# CIC_Arduino_Adapter.net
KiCad netlist of a schematic drawn in EAGLE
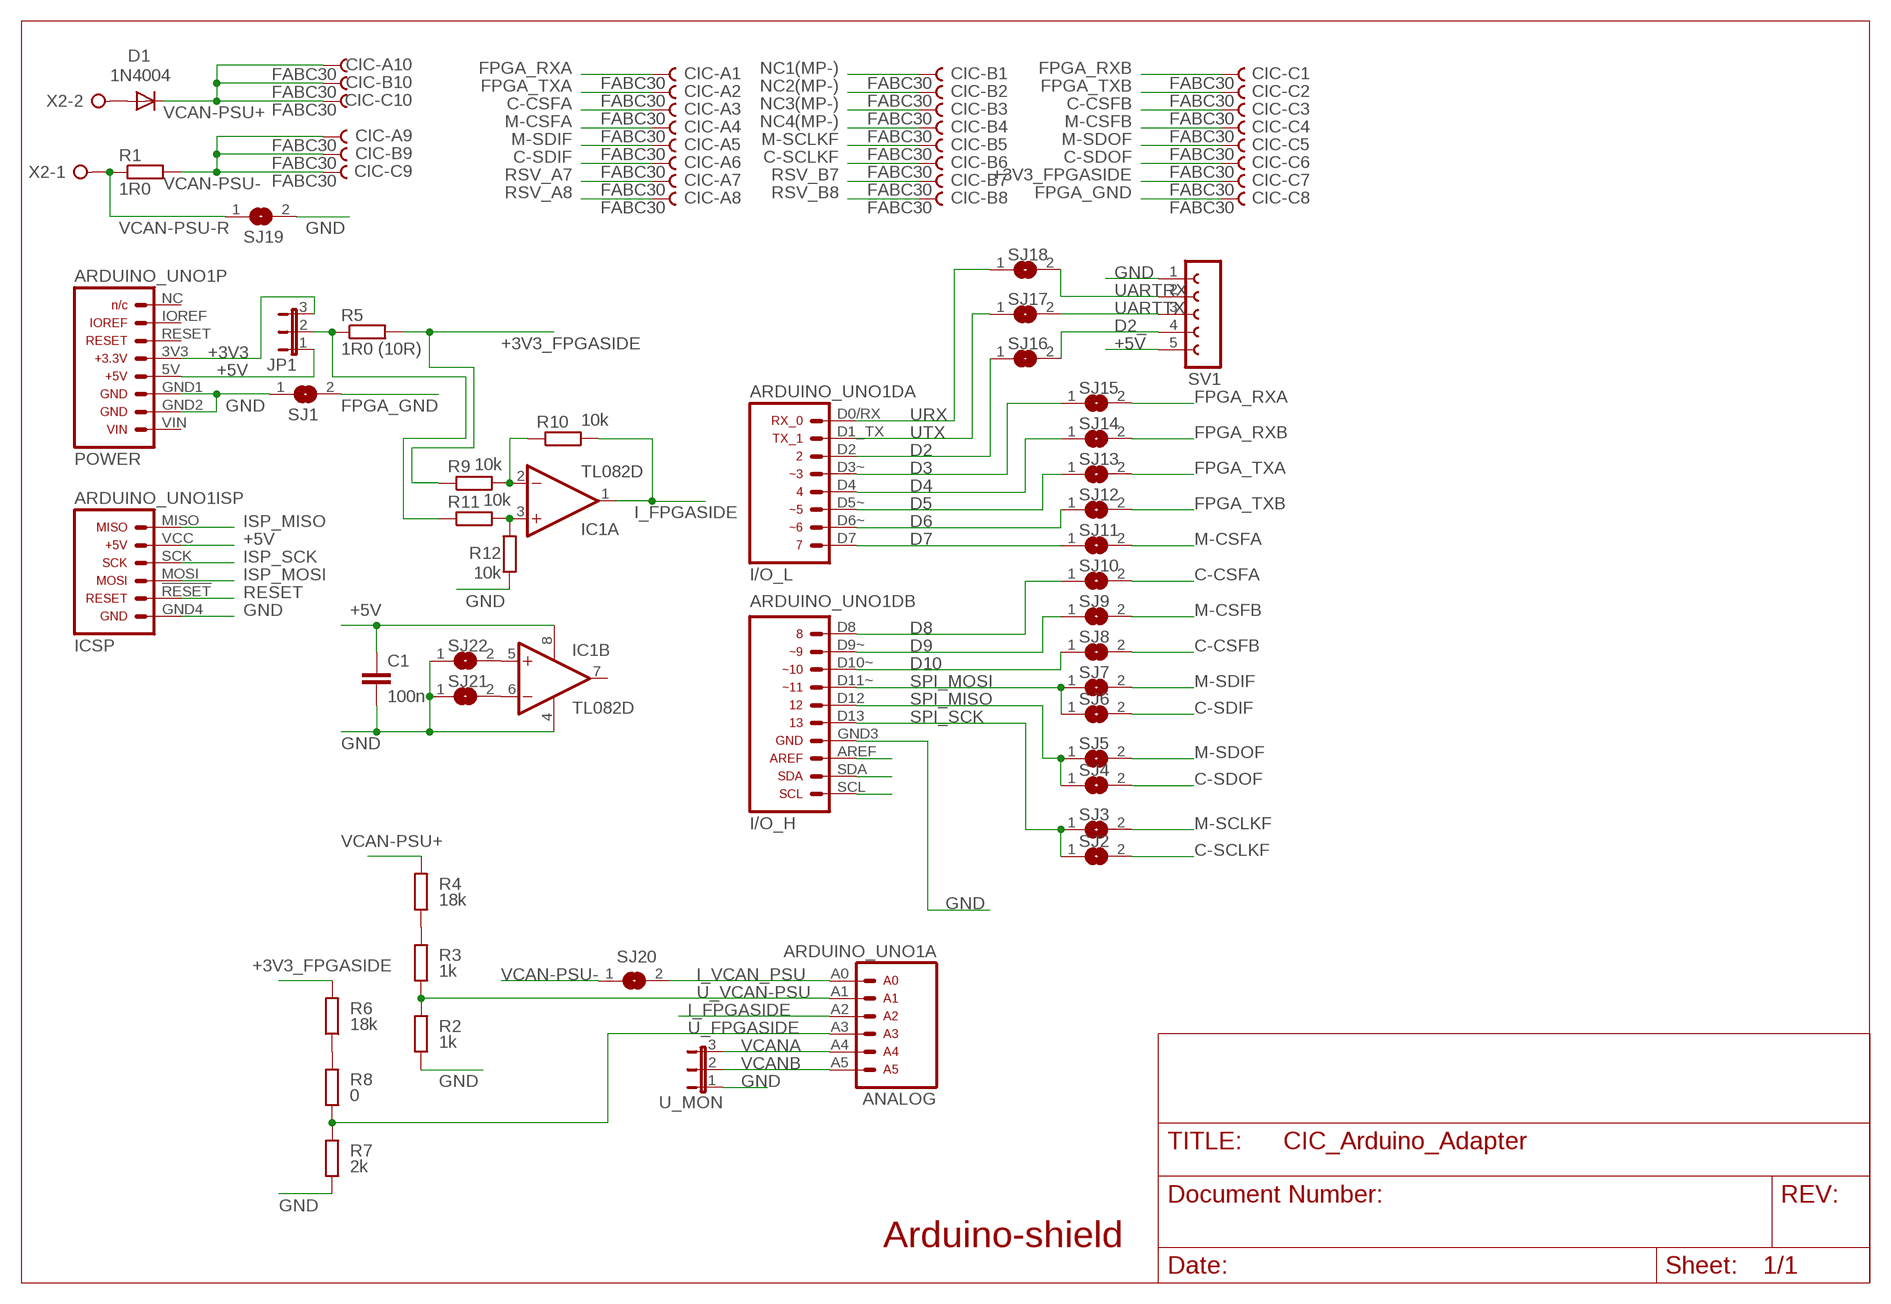
[diagram p0: schematic, sheet 1]

(export (version "E")
  (design (tool "Eeschema 10.0.6"))
  (components
    (comp (ref "ARDUINO_UNO1")
      (value "SHELL_UNO1")
      (footprint "eagle-import:SHELL_UNO_1")
      (libsource (lib "eagle-import") (part "SHELL_UNO1"))
    )
    (comp (ref "C1")
      (value "100n")
      (footprint "eagle-import:C0805")
      (libsource (lib "eagle-import") (part "C-EUC0805"))
    )
    (comp (ref "CIC")
      (value "FABC30")
      (footprint "eagle-import:FABC30")
      (libsource (lib "eagle-import") (part "FABC30"))
    )
    (comp (ref "D1")
      (value "1N4004")
      (footprint "eagle-import:DO41-10")
      (libsource (lib "eagle-import") (part "1N4004"))
    )
    (comp (ref "IC1")
      (value "TL082D")
      (footprint "eagle-import:SO08")
      (libsource (lib "eagle-import") (part "TL082D"))
    )
    (comp (ref "JP1")
      (value "JP2E")
      (footprint "eagle-import:JP2")
      (libsource (lib "eagle-import") (part "JP2E"))
    )
    (comp (ref "R1")
      (value "1R0")
      (footprint "eagle-import:0207_2V")
      (libsource (lib "eagle-import") (part "R-EU_0207/2V"))
    )
    (comp (ref "R2")
      (value "1k")
      (footprint "eagle-import:0207_2V")
      (libsource (lib "eagle-import") (part "R-EU_0207/2V"))
    )
    (comp (ref "R3")
      (value "1k")
      (footprint "eagle-import:0207_2V")
      (libsource (lib "eagle-import") (part "R-EU_0207/2V"))
    )
    (comp (ref "R4")
      (value "18k")
      (footprint "eagle-import:0207_2V")
      (libsource (lib "eagle-import") (part "R-EU_0207/2V"))
    )
    (comp (ref "R5")
      (value "1R0 (10R)")
      (footprint "eagle-import:0207_2V")
      (libsource (lib "eagle-import") (part "R-EU_0207/2V"))
    )
    (comp (ref "R6")
      (value "18k")
      (footprint "eagle-import:0207_2V")
      (libsource (lib "eagle-import") (part "R-EU_0207/2V"))
    )
    (comp (ref "R7")
      (value "2k")
      (footprint "eagle-import:0207_2V")
      (libsource (lib "eagle-import") (part "R-EU_0207/2V"))
    )
    (comp (ref "R8")
      (value "0")
      (footprint "eagle-import:0207_2V")
      (libsource (lib "eagle-import") (part "R-EU_0207/2V"))
    )
    (comp (ref "R9")
      (value "10k")
      (footprint "eagle-import:R0805")
      (libsource (lib "eagle-import") (part "R-EU_R0805"))
    )
    (comp (ref "R10")
      (value "10k")
      (footprint "eagle-import:R0805")
      (libsource (lib "eagle-import") (part "R-EU_R0805"))
    )
    (comp (ref "R11")
      (value "10k")
      (footprint "eagle-import:R0805")
      (libsource (lib "eagle-import") (part "R-EU_R0805"))
    )
    (comp (ref "R12")
      (value "10k")
      (footprint "eagle-import:R0805")
      (libsource (lib "eagle-import") (part "R-EU_R0805"))
    )
    (comp (ref "SJ1") (value "SJ") (footprint "eagle-import:SJ") (libsource (lib "eagle-import") (part "SJ")))
    (comp (ref "SJ2") (value "SJ") (footprint "eagle-import:SJ") (libsource (lib "eagle-import") (part "SJ")))
    (comp (ref "SJ3") (value "SJ") (footprint "eagle-import:SJ") (libsource (lib "eagle-import") (part "SJ")))
    (comp (ref "SJ4") (value "SJ") (footprint "eagle-import:SJ") (libsource (lib "eagle-import") (part "SJ")))
    (comp (ref "SJ5") (value "SJ") (footprint "eagle-import:SJ") (libsource (lib "eagle-import") (part "SJ")))
    (comp (ref "SJ6") (value "SJ") (footprint "eagle-import:SJ") (libsource (lib "eagle-import") (part "SJ")))
    (comp (ref "SJ7") (value "SJ") (footprint "eagle-import:SJ") (libsource (lib "eagle-import") (part "SJ")))
    (comp (ref "SJ8") (value "SJ") (footprint "eagle-import:SJ") (libsource (lib "eagle-import") (part "SJ")))
    (comp (ref "SJ9") (value "SJ") (footprint "eagle-import:SJ") (libsource (lib "eagle-import") (part "SJ")))
    (comp (ref "SJ10")
      (value "SJ")
      (footprint "eagle-import:SJ")
      (libsource (lib "eagle-import") (part "SJ"))
    )
    (comp (ref "SJ11")
      (value "SJ")
      (footprint "eagle-import:SJ")
      (libsource (lib "eagle-import") (part "SJ"))
    )
    (comp (ref "SJ12")
      (value "SJ")
      (footprint "eagle-import:SJ")
      (libsource (lib "eagle-import") (part "SJ"))
    )
    (comp (ref "SJ13")
      (value "SJ")
      (footprint "eagle-import:SJ")
      (libsource (lib "eagle-import") (part "SJ"))
    )
    (comp (ref "SJ14")
      (value "SJ")
      (footprint "eagle-import:SJ")
      (libsource (lib "eagle-import") (part "SJ"))
    )
    (comp (ref "SJ15")
      (value "SJ")
      (footprint "eagle-import:SJ")
      (libsource (lib "eagle-import") (part "SJ"))
    )
    (comp (ref "SJ16")
      (value "SJ")
      (footprint "eagle-import:SJ")
      (libsource (lib "eagle-import") (part "SJ"))
    )
    (comp (ref "SJ17")
      (value "SJ")
      (footprint "eagle-import:SJ")
      (libsource (lib "eagle-import") (part "SJ"))
    )
    (comp (ref "SJ18")
      (value "SJ")
      (footprint "eagle-import:SJ")
      (libsource (lib "eagle-import") (part "SJ"))
    )
    (comp (ref "SJ19")
      (value "SJ")
      (footprint "eagle-import:SJ")
      (libsource (lib "eagle-import") (part "SJ"))
    )
    (comp (ref "SJ20")
      (value "SJ")
      (footprint "eagle-import:SJ")
      (libsource (lib "eagle-import") (part "SJ"))
    )
    (comp (ref "SJ21")
      (value "SJ")
      (footprint "eagle-import:SJ")
      (libsource (lib "eagle-import") (part "SJ"))
    )
    (comp (ref "SJ22")
      (value "SJ")
      (footprint "eagle-import:SJ")
      (libsource (lib "eagle-import") (part "SJ"))
    )
    (comp (ref "SV1")
      (value "FE05-1")
      (footprint "eagle-import:FE05-1")
      (libsource (lib "eagle-import") (part "FE05-1"))
    )
    (comp (ref "U_MON")
      (value "JP2E")
      (footprint "eagle-import:JP2")
      (libsource (lib "eagle-import") (part "JP2E"))
    )
    (comp (ref "X2")
      (value "W237-2N")
      (footprint "eagle-import:W237-2N")
      (libsource (lib "eagle-import") (part "W237-2N"))
    )
  )
  (nets
    (net (code "1") (name "/+3V3") (class "Default")
      (node (ref "ARDUINO_UNO1") (pin "3V3") (pinfunction "4_3V3") (pintype "passive"))
      (node (ref "JP1") (pin "3") (pinfunction "3_3") (pintype "passive"))
    )
    (net (code "2") (name "/+3V3_FPGASIDE") (class "Default")
      (node (ref "CIC") (pin "C7") (pinfunction "B_C7") (pintype "passive"))
      (node (ref "R5") (pin "2") (pinfunction "2_2") (pintype "passive"))
      (node (ref "R6") (pin "2") (pinfunction "2_2") (pintype "passive"))
      (node (ref "R9") (pin "1") (pinfunction "1_1") (pintype "passive"))
    )
    (net (code "3") (name "/+5V") (class "Default")
      (node (ref "ARDUINO_UNO1") (pin "5V") (pinfunction "5_5V") (pintype "passive"))
      (node (ref "ARDUINO_UNO1") (pin "VCC") (pinfunction "2_VCC") (pintype "passive"))
      (node (ref "C1") (pin "1") (pinfunction "1_1") (pintype "passive"))
      (node (ref "IC1") (pin "8") (pinfunction "V+_8") (pintype "power_in"))
      (node (ref "JP1") (pin "1") (pinfunction "1_1") (pintype "passive"))
      (node (ref "SV1") (pin "5") (pinfunction "5_5") (pintype "passive"))
    )
    (net (code "4") (name "/C-CSFA") (class "Default")
      (node (ref "CIC") (pin "A3") (pinfunction "B_A3") (pintype "passive"))
      (node (ref "SJ10") (pin "2") (pinfunction "2_2") (pintype "passive"))
    )
    (net (code "5") (name "/C-CSFB") (class "Default")
      (node (ref "CIC") (pin "C3") (pinfunction "B_C3") (pintype "passive"))
      (node (ref "SJ8") (pin "2") (pinfunction "2_2") (pintype "passive"))
    )
    (net (code "6") (name "/C-SCLKF") (class "Default")
      (node (ref "CIC") (pin "B6") (pinfunction "B_B6") (pintype "passive"))
      (node (ref "SJ2") (pin "2") (pinfunction "2_2") (pintype "passive"))
    )
    (net (code "7") (name "/C-SDIF") (class "Default")
      (node (ref "CIC") (pin "A6") (pinfunction "B_A6") (pintype "passive"))
      (node (ref "SJ6") (pin "2") (pinfunction "2_2") (pintype "passive"))
    )
    (net (code "8") (name "/C-SDOF") (class "Default")
      (node (ref "CIC") (pin "C6") (pinfunction "B_C6") (pintype "passive"))
      (node (ref "SJ4") (pin "2") (pinfunction "2_2") (pintype "passive"))
    )
    (net (code "9") (name "/D2") (class "Default")
      (node (ref "ARDUINO_UNO1") (pin "D2") (pinfunction "3_D2") (pintype "passive"))
      (node (ref "SJ16") (pin "1") (pinfunction "1_1") (pintype "passive"))
    )
    (net (code "10") (name "/D2_") (class "Default")
      (node (ref "SJ16") (pin "2") (pinfunction "2_2") (pintype "passive"))
      (node (ref "SV1") (pin "4") (pinfunction "4_4") (pintype "passive"))
    )
    (net (code "11") (name "/D3") (class "Default")
      (node (ref "ARDUINO_UNO1") (pin "D3~") (pinfunction "4_D3~") (pintype "passive"))
      (node (ref "SJ15") (pin "1") (pinfunction "1_1") (pintype "passive"))
    )
    (net (code "12") (name "/D4") (class "Default")
      (node (ref "ARDUINO_UNO1") (pin "D4") (pinfunction "5_D4") (pintype "passive"))
      (node (ref "SJ14") (pin "1") (pinfunction "1_1") (pintype "passive"))
    )
    (net (code "13") (name "/D5") (class "Default")
      (node (ref "ARDUINO_UNO1") (pin "D5~") (pinfunction "6_D5~") (pintype "passive"))
      (node (ref "SJ13") (pin "1") (pinfunction "1_1") (pintype "passive"))
    )
    (net (code "14") (name "/D6") (class "Default")
      (node (ref "ARDUINO_UNO1") (pin "D6~") (pinfunction "7_D6~") (pintype "passive"))
      (node (ref "SJ12") (pin "1") (pinfunction "1_1") (pintype "passive"))
    )
    (net (code "15") (name "/D7") (class "Default")
      (node (ref "ARDUINO_UNO1") (pin "D7") (pinfunction "8_D7") (pintype "passive"))
      (node (ref "SJ11") (pin "1") (pinfunction "1_1") (pintype "passive"))
    )
    (net (code "16") (name "/D8") (class "Default")
      (node (ref "ARDUINO_UNO1") (pin "D8") (pinfunction "1_D8") (pintype "passive"))
      (node (ref "SJ10") (pin "1") (pinfunction "1_1") (pintype "passive"))
    )
    (net (code "17") (name "/D9") (class "Default")
      (node (ref "ARDUINO_UNO1") (pin "D9~") (pinfunction "2_D9~") (pintype "passive"))
      (node (ref "SJ9") (pin "1") (pinfunction "1_1") (pintype "passive"))
    )
    (net (code "18") (name "/D10") (class "Default")
      (node (ref "ARDUINO_UNO1") (pin "D10~") (pinfunction "3_D10~") (pintype "passive"))
      (node (ref "SJ8") (pin "1") (pinfunction "1_1") (pintype "passive"))
    )
    (net (code "19") (name "/FPGA_GND") (class "Default")
      (node (ref "CIC") (pin "C8") (pinfunction "B_C8") (pintype "passive"))
      (node (ref "SJ1") (pin "2") (pinfunction "2_2") (pintype "passive"))
    )
    (net (code "20") (name "/FPGA_RXA") (class "Default")
      (node (ref "CIC") (pin "A1") (pinfunction "B_A1") (pintype "passive"))
      (node (ref "SJ15") (pin "2") (pinfunction "2_2") (pintype "passive"))
    )
    (net (code "21") (name "/FPGA_RXB") (class "Default")
      (node (ref "CIC") (pin "C1") (pinfunction "B_C1") (pintype "passive"))
      (node (ref "SJ14") (pin "2") (pinfunction "2_2") (pintype "passive"))
    )
    (net (code "22") (name "/FPGA_TXA") (class "Default")
      (node (ref "CIC") (pin "A2") (pinfunction "B_A2") (pintype "passive"))
      (node (ref "SJ13") (pin "2") (pinfunction "2_2") (pintype "passive"))
    )
    (net (code "23") (name "/FPGA_TXB") (class "Default")
      (node (ref "CIC") (pin "C2") (pinfunction "B_C2") (pintype "passive"))
      (node (ref "SJ12") (pin "2") (pinfunction "2_2") (pintype "passive"))
    )
    (net (code "24") (name "/GND") (class "Default")
      (node (ref "ARDUINO_UNO1") (pin "GND1") (pinfunction "6_GND1") (pintype "passive"))
      (node (ref "ARDUINO_UNO1") (pin "GND2") (pinfunction "7_GND2") (pintype "passive"))
      (node (ref "ARDUINO_UNO1") (pin "GND3") (pinfunction "7_GND3") (pintype "passive"))
      (node (ref "ARDUINO_UNO1") (pin "GND4") (pinfunction "6_GND4") (pintype "passive"))
      (node (ref "C1") (pin "2") (pinfunction "2_2") (pintype "passive"))
      (node (ref "IC1") (pin "4") (pinfunction "V-_4") (pintype "power_in"))
      (node (ref "R12") (pin "1") (pinfunction "1_1") (pintype "passive"))
      (node (ref "R2") (pin "1") (pinfunction "1_1") (pintype "passive"))
      (node (ref "R7") (pin "1") (pinfunction "1_1") (pintype "passive"))
      (node (ref "SJ1") (pin "1") (pinfunction "1_1") (pintype "passive"))
      (node (ref "SJ19") (pin "2") (pinfunction "2_2") (pintype "passive"))
      (node (ref "SJ21") (pin "1") (pinfunction "1_1") (pintype "passive"))
      (node (ref "SJ22") (pin "1") (pinfunction "1_1") (pintype "passive"))
      (node (ref "SV1") (pin "1") (pinfunction "1_1") (pintype "passive"))
      (node (ref "U_MON") (pin "1") (pinfunction "1_1") (pintype "passive"))
    )
    (net (code "25") (name "/ISP_MISO") (class "Default")
      (node (ref "ARDUINO_UNO1") (pin "MISO") (pinfunction "1_MISO") (pintype "passive"))
    )
    (net (code "26") (name "/ISP_MOSI") (class "Default")
      (node (ref "ARDUINO_UNO1") (pin "MOSI") (pinfunction "4_MOSI") (pintype "passive"))
    )
    (net (code "27") (name "/ISP_SCK") (class "Default")
      (node (ref "ARDUINO_UNO1") (pin "SCK") (pinfunction "3_SCK") (pintype "passive"))
    )
    (net (code "28") (name "/I_FPGASIDE") (class "Default")
      (node (ref "ARDUINO_UNO1") (pin "A2") (pinfunction "3_A2") (pintype "passive"))
      (node (ref "IC1") (pin "1") (pinfunction "OUT_1") (pintype "output"))
      (node (ref "R10") (pin "2") (pinfunction "2_2") (pintype "passive"))
    )
    (net (code "29") (name "/I_VCAN_PSU") (class "Default")
      (node (ref "ARDUINO_UNO1") (pin "A0") (pinfunction "1_A0") (pintype "passive"))
      (node (ref "SJ20") (pin "2") (pinfunction "2_2") (pintype "passive"))
    )
    (net (code "30") (name "/M-CSFA") (class "Default")
      (node (ref "CIC") (pin "A4") (pinfunction "B_A4") (pintype "passive"))
      (node (ref "SJ11") (pin "2") (pinfunction "2_2") (pintype "passive"))
    )
    (net (code "31") (name "/M-CSFB") (class "Default")
      (node (ref "CIC") (pin "C4") (pinfunction "B_C4") (pintype "passive"))
      (node (ref "SJ9") (pin "2") (pinfunction "2_2") (pintype "passive"))
    )
    (net (code "32") (name "/M-SCLKF") (class "Default")
      (node (ref "CIC") (pin "B5") (pinfunction "B_B5") (pintype "passive"))
      (node (ref "SJ3") (pin "2") (pinfunction "2_2") (pintype "passive"))
    )
    (net (code "33") (name "/M-SDIF") (class "Default")
      (node (ref "CIC") (pin "A5") (pinfunction "B_A5") (pintype "passive"))
      (node (ref "SJ7") (pin "2") (pinfunction "2_2") (pintype "passive"))
    )
    (net (code "34") (name "/M-SDOF") (class "Default")
      (node (ref "CIC") (pin "C5") (pinfunction "B_C5") (pintype "passive"))
      (node (ref "SJ5") (pin "2") (pinfunction "2_2") (pintype "passive"))
    )
    (net (code "35") (name "/NC1(MP-)") (class "Default")
      (node (ref "CIC") (pin "B1") (pinfunction "B_B1") (pintype "passive"))
    )
    (net (code "36") (name "/NC2(MP-)") (class "Default")
      (node (ref "CIC") (pin "B2") (pinfunction "B_B2") (pintype "passive"))
    )
    (net (code "37") (name "/NC3(MP-)") (class "Default")
      (node (ref "CIC") (pin "B3") (pinfunction "B_B3") (pintype "passive"))
    )
    (net (code "38") (name "/NC4(MP-)") (class "Default")
      (node (ref "CIC") (pin "B4") (pinfunction "B_B4") (pintype "passive"))
    )
    (net (code "39") (name "/RESET") (class "Default")
      (node (ref "ARDUINO_UNO1") (pin "!RESET") (pinfunction "5_!RESET") (pintype "passive"))
    )
    (net (code "40") (name "/RSV_A7") (class "Default")
      (node (ref "CIC") (pin "A7") (pinfunction "B_A7") (pintype "passive"))
    )
    (net (code "41") (name "/RSV_A8") (class "Default")
      (node (ref "CIC") (pin "A8") (pinfunction "B_A8") (pintype "passive"))
    )
    (net (code "42") (name "/RSV_B7") (class "Default")
      (node (ref "CIC") (pin "B7") (pinfunction "B_B7") (pintype "passive"))
    )
    (net (code "43") (name "/RSV_B8") (class "Default")
      (node (ref "CIC") (pin "B8") (pinfunction "B_B8") (pintype "passive"))
    )
    (net (code "44") (name "/SPI_MISO") (class "Default")
      (node (ref "ARDUINO_UNO1") (pin "D12") (pinfunction "5_D12") (pintype "passive"))
      (node (ref "SJ4") (pin "1") (pinfunction "1_1") (pintype "passive"))
      (node (ref "SJ5") (pin "1") (pinfunction "1_1") (pintype "passive"))
    )
    (net (code "45") (name "/SPI_MOSI") (class "Default")
      (node (ref "ARDUINO_UNO1") (pin "D11~") (pinfunction "4_D11~") (pintype "passive"))
      (node (ref "SJ6") (pin "1") (pinfunction "1_1") (pintype "passive"))
      (node (ref "SJ7") (pin "1") (pinfunction "1_1") (pintype "passive"))
    )
    (net (code "46") (name "/SPI_SCK") (class "Default")
      (node (ref "ARDUINO_UNO1") (pin "D13") (pinfunction "6_D13") (pintype "passive"))
      (node (ref "SJ2") (pin "1") (pinfunction "1_1") (pintype "passive"))
      (node (ref "SJ3") (pin "1") (pinfunction "1_1") (pintype "passive"))
    )
    (net (code "47") (name "/UARTRX") (class "Default")
      (node (ref "SJ18") (pin "2") (pinfunction "2_2") (pintype "passive"))
      (node (ref "SV1") (pin "2") (pinfunction "2_2") (pintype "passive"))
    )
    (net (code "48") (name "/UARTTX") (class "Default")
      (node (ref "SJ17") (pin "2") (pinfunction "2_2") (pintype "passive"))
      (node (ref "SV1") (pin "3") (pinfunction "3_3") (pintype "passive"))
    )
    (net (code "49") (name "/URX") (class "Default")
      (node (ref "ARDUINO_UNO1") (pin "D0/RX") (pinfunction "1_D0/RX") (pintype "passive"))
      (node (ref "SJ18") (pin "1") (pinfunction "1_1") (pintype "passive"))
    )
    (net (code "50") (name "/UTX") (class "Default")
      (node (ref "ARDUINO_UNO1") (pin "D1_TX") (pinfunction "2_D1_TX") (pintype "passive"))
      (node (ref "SJ17") (pin "1") (pinfunction "1_1") (pintype "passive"))
    )
    (net (code "51") (name "/U_FPGASIDE") (class "Default")
      (node (ref "ARDUINO_UNO1") (pin "A3") (pinfunction "4_A3") (pintype "passive"))
      (node (ref "R7") (pin "2") (pinfunction "2_2") (pintype "passive"))
      (node (ref "R8") (pin "1") (pinfunction "1_1") (pintype "passive"))
    )
    (net (code "52") (name "/U_VCAN-PSU") (class "Default")
      (node (ref "ARDUINO_UNO1") (pin "A1") (pinfunction "2_A1") (pintype "passive"))
      (node (ref "R2") (pin "2") (pinfunction "2_2") (pintype "passive"))
      (node (ref "R3") (pin "1") (pinfunction "1_1") (pintype "passive"))
    )
    (net (code "53") (name "/VCAN-PSU+") (class "Default")
      (node (ref "CIC") (pin "A10") (pinfunction "B_A10") (pintype "passive"))
      (node (ref "CIC") (pin "B10") (pinfunction "B_B10") (pintype "passive"))
      (node (ref "CIC") (pin "C10") (pinfunction "B_C10") (pintype "passive"))
      (node (ref "D1") (pin "C") (pinfunction "C_C") (pintype "passive"))
      (node (ref "R4") (pin "2") (pinfunction "2_2") (pintype "passive"))
    )
    (net (code "54") (name "/VCAN-PSU-") (class "Default")
      (node (ref "CIC") (pin "A9") (pinfunction "B_A9") (pintype "passive"))
      (node (ref "CIC") (pin "B9") (pinfunction "B_B9") (pintype "passive"))
      (node (ref "CIC") (pin "C9") (pinfunction "B_C9") (pintype "passive"))
      (node (ref "R1") (pin "2") (pinfunction "2_2") (pintype "passive"))
      (node (ref "SJ20") (pin "1") (pinfunction "1_1") (pintype "passive"))
    )
    (net (code "55") (name "/VCAN-PSU-R") (class "Default")
      (node (ref "R1") (pin "1") (pinfunction "1_1") (pintype "passive"))
      (node (ref "SJ19") (pin "1") (pinfunction "1_1") (pintype "passive"))
      (node (ref "X2") (pin "1") (pinfunction "KL_1") (pintype "passive"))
    )
    (net (code "56") (name "/VCANA") (class "Default")
      (node (ref "ARDUINO_UNO1") (pin "A4") (pinfunction "5_A4") (pintype "passive"))
      (node (ref "U_MON") (pin "3") (pinfunction "3_3") (pintype "passive"))
    )
    (net (code "57") (name "/VCANB") (class "Default")
      (node (ref "ARDUINO_UNO1") (pin "A5") (pinfunction "6_A5") (pintype "passive"))
      (node (ref "U_MON") (pin "2") (pinfunction "2_2") (pintype "passive"))
    )
    (net (code "58") (name "Net-(IC1A-+IN)") (class "Default")
      (node (ref "IC1") (pin "3") (pinfunction "+IN_3") (pintype "input"))
      (node (ref "R11") (pin "2") (pinfunction "2_2") (pintype "passive"))
      (node (ref "R12") (pin "2") (pinfunction "2_2") (pintype "passive"))
    )
    (net (code "59") (name "Net-(IC1A--IN)") (class "Default")
      (node (ref "IC1") (pin "2") (pinfunction "-IN_2") (pintype "input"))
      (node (ref "R10") (pin "1") (pinfunction "1_1") (pintype "passive"))
      (node (ref "R9") (pin "2") (pinfunction "2_2") (pintype "passive"))
    )
    (net (code "60") (name "Net-(IC1B-+IN)") (class "Default")
      (node (ref "IC1") (pin "5") (pinfunction "+IN_5") (pintype "input"))
      (node (ref "SJ22") (pin "2") (pinfunction "2_2") (pintype "passive"))
    )
    (net (code "61") (name "Net-(IC1B--IN)") (class "Default")
      (node (ref "IC1") (pin "6") (pinfunction "-IN_6") (pintype "input"))
      (node (ref "SJ21") (pin "2") (pinfunction "2_2") (pintype "passive"))
    )
    (net (code "62") (name "Net-(JP1-Pad2)") (class "Default")
      (node (ref "JP1") (pin "2") (pinfunction "2_2") (pintype "passive"))
      (node (ref "R11") (pin "1") (pinfunction "1_1") (pintype "passive"))
      (node (ref "R5") (pin "1") (pinfunction "1_1") (pintype "passive"))
    )
    (net (code "63") (name "Net-(R3-Pad2)") (class "Default")
      (node (ref "R3") (pin "2") (pinfunction "2_2") (pintype "passive"))
      (node (ref "R4") (pin "1") (pinfunction "1_1") (pintype "passive"))
    )
    (net (code "64") (name "Net-(R6-Pad1)") (class "Default")
      (node (ref "R6") (pin "1") (pinfunction "1_1") (pintype "passive"))
      (node (ref "R8") (pin "2") (pinfunction "2_2") (pintype "passive"))
    )
    (net (code "65") (name "Net-(X2B-KL)") (class "Default")
      (node (ref "D1") (pin "A") (pinfunction "A_A") (pintype "passive"))
      (node (ref "X2") (pin "2") (pinfunction "KL_2") (pintype "passive"))
    )
    (net (code "66") (name "unconnected-(ARDUINO_UNO1C-8-PadAREF)") (class "Default")
      (node (ref "ARDUINO_UNO1") (pin "AREF") (pinfunction "8_AREF") (pintype "passive"))
    )
    (net (code "67") (name "unconnected-(ARDUINO_UNO1C-9-PadSDA)") (class "Default")
      (node (ref "ARDUINO_UNO1") (pin "SDA") (pinfunction "9_SDA") (pintype "passive"))
    )
    (net (code "68") (name "unconnected-(ARDUINO_UNO1C-10-PadSCL)") (class "Default")
      (node (ref "ARDUINO_UNO1") (pin "SCL") (pinfunction "10_SCL") (pintype "passive"))
    )
    (net (code "69") (name "unconnected-(ARDUINO_UNO1E-1-PadNC)") (class "Default")
      (node (ref "ARDUINO_UNO1") (pin "NC") (pinfunction "1_NC") (pintype "passive"))
    )
    (net (code "70") (name "unconnected-(ARDUINO_UNO1E-2-PadIOREF)") (class "Default")
      (node (ref "ARDUINO_UNO1") (pin "IOREF") (pinfunction "2_IOREF") (pintype "passive"))
    )
    (net (code "71") (name "unconnected-(ARDUINO_UNO1E-3-PadRESET)") (class "Default")
      (node (ref "ARDUINO_UNO1") (pin "RESET") (pinfunction "3_RESET") (pintype "passive"))
    )
    (net (code "72") (name "unconnected-(ARDUINO_UNO1E-8-PadVIN)") (class "Default")
      (node (ref "ARDUINO_UNO1") (pin "VIN") (pinfunction "8_VIN") (pintype "passive"))
    )
    (net (code "73") (name "unconnected-(IC1B-OUT-Pad7)") (class "Default")
      (node (ref "IC1") (pin "7") (pinfunction "OUT_7") (pintype "output"))
    )
  )
)
